# V_5.net
KiCad netlist of a schematic drawn in Altium Designer
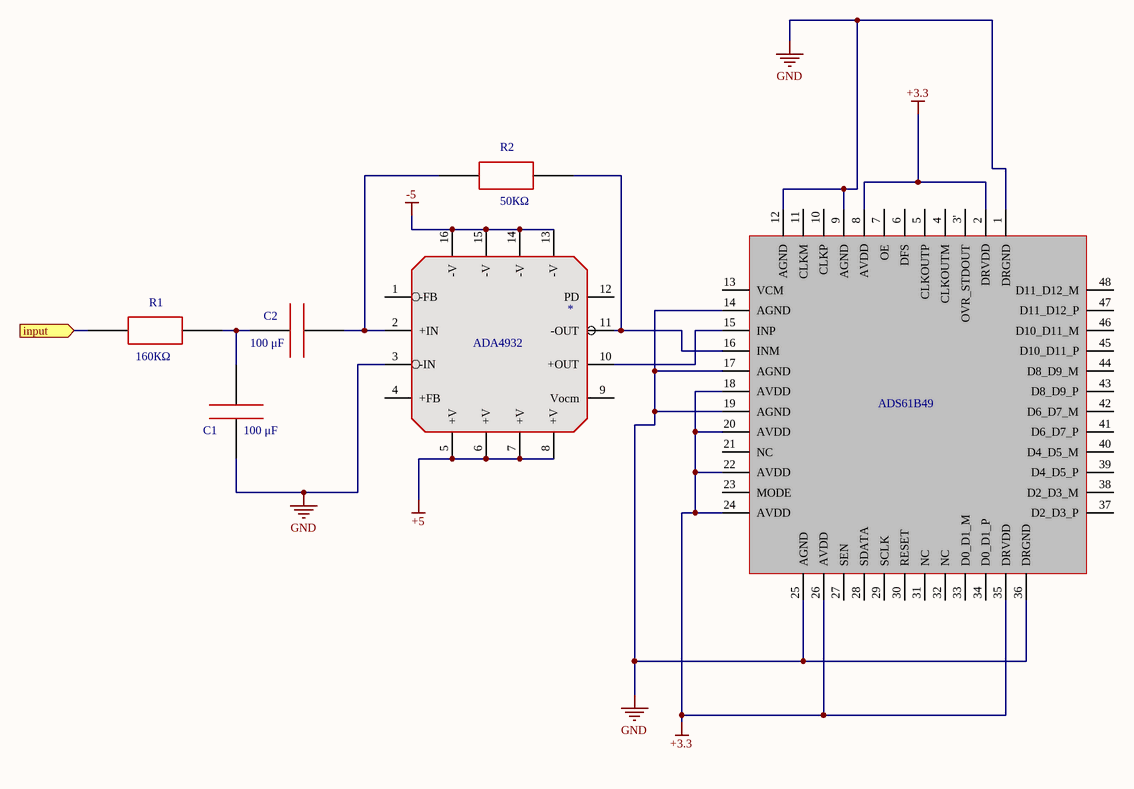
[diagram p0: V_5.SchDoc]

(export (version "E")
  (design (tool "Eeschema 10.0.6"))
  (components
    (comp (ref "ADA4932") (value "*") (footprint "ADA4932") (libsource (lib "*") (part "ADA4932")))
    (comp (ref "ADS61B49") (value "*") (footprint "ADS61B49") (libsource (lib "*") (part "ADS61B49")))
    (comp (ref "C1") (value "100 μF") (footprint "Capacitor") (libsource (lib "*") (part "Capacitor")))
    (comp (ref "C2") (value "100 μF") (footprint "Capacitor") (libsource (lib "*") (part "Capacitor")))
    (comp (ref "R1") (value "160КΩ") (footprint "Resistor") (libsource (lib "*") (part "Resistor")))
    (comp (ref "R2") (value "50КΩ") (footprint "Resistor") (libsource (lib "*") (part "Resistor")))
  )
  (nets
    (net (code "1") (name "+3.3") (class "Default")
      (node (ref "ADS61B49") (pin "18") (pinfunction "AVDD_18") (pintype "passive"))
      (node (ref "ADS61B49") (pin "2") (pinfunction "DRVDD_2") (pintype "passive"))
      (node (ref "ADS61B49") (pin "20") (pinfunction "AVDD_20") (pintype "passive"))
      (node (ref "ADS61B49") (pin "22") (pinfunction "AVDD_22") (pintype "passive"))
      (node (ref "ADS61B49") (pin "24") (pinfunction "AVDD_24") (pintype "passive"))
      (node (ref "ADS61B49") (pin "26") (pinfunction "AVDD_26") (pintype "passive"))
      (node (ref "ADS61B49") (pin "35") (pinfunction "DRVDD_35") (pintype "passive"))
      (node (ref "ADS61B49") (pin "8") (pinfunction "AVDD_8") (pintype "passive"))
    )
    (net (code "2") (name "+5") (class "Default")
      (node (ref "ADA4932") (pin "5") (pinfunction "+V_5") (pintype "passive"))
      (node (ref "ADA4932") (pin "6") (pinfunction "+V_6") (pintype "passive"))
      (node (ref "ADA4932") (pin "7") (pinfunction "+V_7") (pintype "passive"))
      (node (ref "ADA4932") (pin "8") (pinfunction "+V_8") (pintype "passive"))
    )
    (net (code "3") (name "-5") (class "Default")
      (node (ref "ADA4932") (pin "13") (pinfunction "-V_13") (pintype "passive"))
      (node (ref "ADA4932") (pin "14") (pinfunction "-V_14") (pintype "passive"))
      (node (ref "ADA4932") (pin "15") (pinfunction "-V_15") (pintype "passive"))
      (node (ref "ADA4932") (pin "16") (pinfunction "-V_16") (pintype "passive"))
    )
    (net (code "4") (name "/input") (class "Default")
      (node (ref "R1") (pin "0") (pinfunction "0_0") (pintype "passive"))
    )
    (net (code "5") (name "GND") (class "Default")
      (node (ref "ADA4932") (pin "3") (pinfunction "-IN_3") (pintype "passive"))
      (node (ref "ADS61B49") (pin "1") (pinfunction "DRGND_1") (pintype "passive"))
      (node (ref "ADS61B49") (pin "12") (pinfunction "AGND_12") (pintype "passive"))
      (node (ref "ADS61B49") (pin "14") (pinfunction "AGND_14") (pintype "passive"))
      (node (ref "ADS61B49") (pin "17") (pinfunction "AGND_17") (pintype "passive"))
      (node (ref "ADS61B49") (pin "19") (pinfunction "AGND_19") (pintype "passive"))
      (node (ref "ADS61B49") (pin "25") (pinfunction "AGND_25") (pintype "passive"))
      (node (ref "ADS61B49") (pin "36") (pinfunction "DRGND_36") (pintype "passive"))
      (node (ref "ADS61B49") (pin "9") (pinfunction "AGND_9") (pintype "passive"))
      (node (ref "C1") (pin "3") (pinfunction "3_3") (pintype "passive"))
    )
    (net (code "6") (name "Net-(ADA4932-+IN)") (class "Default")
      (node (ref "ADA4932") (pin "2") (pinfunction "+IN_2") (pintype "passive"))
      (node (ref "C2") (pin "2") (pinfunction "2_2") (pintype "passive"))
      (node (ref "R2") (pin "0") (pinfunction "0_0") (pintype "passive"))
    )
    (net (code "7") (name "Net-(ADA4932-+OUT)") (class "Default")
      (node (ref "ADA4932") (pin "10") (pinfunction "+OUT_10") (pintype "passive"))
      (node (ref "ADS61B49") (pin "15") (pinfunction "INP_15") (pintype "passive"))
    )
    (net (code "8") (name "Net-(ADA4932--OUT)") (class "Default")
      (node (ref "ADA4932") (pin "11") (pinfunction "-OUT_11") (pintype "passive"))
      (node (ref "ADS61B49") (pin "16") (pinfunction "INM_16") (pintype "passive"))
      (node (ref "R2") (pin "1") (pinfunction "1_1") (pintype "passive"))
    )
    (net (code "9") (name "Net-(C1-Pad2)") (class "Default")
      (node (ref "C1") (pin "2") (pinfunction "2_2") (pintype "passive"))
      (node (ref "C2") (pin "3") (pinfunction "3_3") (pintype "passive"))
      (node (ref "R1") (pin "1") (pinfunction "1_1") (pintype "passive"))
    )
    (net (code "10") (name "unconnected-(ADA4932-+FB-Pad4)") (class "Default")
      (node (ref "ADA4932") (pin "4") (pinfunction "+FB_4") (pintype "passive"))
    )
    (net (code "11") (name "unconnected-(ADA4932--FB-Pad1)") (class "Default")
      (node (ref "ADA4932") (pin "1") (pinfunction "-FB_1") (pintype "passive"))
    )
    (net (code "12") (name "unconnected-(ADA4932-PD-Pad12)") (class "Default")
      (node (ref "ADA4932") (pin "12") (pinfunction "PD_12") (pintype "passive"))
    )
    (net (code "13") (name "unconnected-(ADA4932-Vocm-Pad9)") (class "Default")
      (node (ref "ADA4932") (pin "9") (pinfunction "Vocm_9") (pintype "passive"))
    )
    (net (code "14") (name "unconnected-(ADS61B49-CLKM-Pad11)") (class "Default")
      (node (ref "ADS61B49") (pin "11") (pinfunction "CLKM_11") (pintype "passive"))
    )
    (net (code "15") (name "unconnected-(ADS61B49-CLKOUTM-Pad4)") (class "Default")
      (node (ref "ADS61B49") (pin "4") (pinfunction "CLKOUTM_4") (pintype "passive"))
    )
    (net (code "16") (name "unconnected-(ADS61B49-CLKOUTP-Pad5)") (class "Default")
      (node (ref "ADS61B49") (pin "5") (pinfunction "CLKOUTP_5") (pintype "passive"))
    )
    (net (code "17") (name "unconnected-(ADS61B49-CLKP-Pad10)") (class "Default")
      (node (ref "ADS61B49") (pin "10") (pinfunction "CLKP_10") (pintype "passive"))
    )
    (net (code "18") (name "unconnected-(ADS61B49-D0_D1_M-Pad33)") (class "Default")
      (node (ref "ADS61B49") (pin "33") (pinfunction "D0_D1_M_33") (pintype "passive"))
    )
    (net (code "19") (name "unconnected-(ADS61B49-D0_D1_P-Pad34)") (class "Default")
      (node (ref "ADS61B49") (pin "34") (pinfunction "D0_D1_P_34") (pintype "passive"))
    )
    (net (code "20") (name "unconnected-(ADS61B49-D2_D3_M-Pad38)") (class "Default")
      (node (ref "ADS61B49") (pin "38") (pinfunction "D2_D3_M_38") (pintype "passive"))
    )
    (net (code "21") (name "unconnected-(ADS61B49-D2_D3_P-Pad37)") (class "Default")
      (node (ref "ADS61B49") (pin "37") (pinfunction "D2_D3_P_37") (pintype "passive"))
    )
    (net (code "22") (name "unconnected-(ADS61B49-D4_D5_M-Pad40)") (class "Default")
      (node (ref "ADS61B49") (pin "40") (pinfunction "D4_D5_M_40") (pintype "passive"))
    )
    (net (code "23") (name "unconnected-(ADS61B49-D4_D5_P-Pad39)") (class "Default")
      (node (ref "ADS61B49") (pin "39") (pinfunction "D4_D5_P_39") (pintype "passive"))
    )
    (net (code "24") (name "unconnected-(ADS61B49-D6_D7_M-Pad42)") (class "Default")
      (node (ref "ADS61B49") (pin "42") (pinfunction "D6_D7_M_42") (pintype "passive"))
    )
    (net (code "25") (name "unconnected-(ADS61B49-D6_D7_P-Pad41)") (class "Default")
      (node (ref "ADS61B49") (pin "41") (pinfunction "D6_D7_P_41") (pintype "passive"))
    )
    (net (code "26") (name "unconnected-(ADS61B49-D8_D9_M-Pad44)") (class "Default")
      (node (ref "ADS61B49") (pin "44") (pinfunction "D8_D9_M_44") (pintype "passive"))
    )
    (net (code "27") (name "unconnected-(ADS61B49-D8_D9_P-Pad43)") (class "Default")
      (node (ref "ADS61B49") (pin "43") (pinfunction "D8_D9_P_43") (pintype "passive"))
    )
    (net (code "28") (name "unconnected-(ADS61B49-D10_D11_M-Pad46)") (class "Default")
      (node (ref "ADS61B49") (pin "46") (pinfunction "D10_D11_M_46") (pintype "passive"))
    )
    (net (code "29") (name "unconnected-(ADS61B49-D10_D11_P-Pad45)") (class "Default")
      (node (ref "ADS61B49") (pin "45") (pinfunction "D10_D11_P_45") (pintype "passive"))
    )
    (net (code "30") (name "unconnected-(ADS61B49-D11_D12_M-Pad48)") (class "Default")
      (node (ref "ADS61B49") (pin "48") (pinfunction "D11_D12_M_48") (pintype "passive"))
    )
    (net (code "31") (name "unconnected-(ADS61B49-D11_D12_P-Pad47)") (class "Default")
      (node (ref "ADS61B49") (pin "47") (pinfunction "D11_D12_P_47") (pintype "passive"))
    )
    (net (code "32") (name "unconnected-(ADS61B49-DFS-Pad6)") (class "Default")
      (node (ref "ADS61B49") (pin "6") (pinfunction "DFS_6") (pintype "passive"))
    )
    (net (code "33") (name "unconnected-(ADS61B49-MODE-Pad23)") (class "Default")
      (node (ref "ADS61B49") (pin "23") (pinfunction "MODE_23") (pintype "passive"))
    )
    (net (code "34") (name "unconnected-(ADS61B49-NC-Pad21)") (class "Default")
      (node (ref "ADS61B49") (pin "21") (pinfunction "NC_21") (pintype "passive"))
    )
    (net (code "35") (name "unconnected-(ADS61B49-NC-Pad31)") (class "Default")
      (node (ref "ADS61B49") (pin "31") (pinfunction "NC_31") (pintype "passive"))
    )
    (net (code "36") (name "unconnected-(ADS61B49-NC-Pad32)") (class "Default")
      (node (ref "ADS61B49") (pin "32") (pinfunction "NC_32") (pintype "passive"))
    )
    (net (code "37") (name "unconnected-(ADS61B49-OE-Pad7)") (class "Default")
      (node (ref "ADS61B49") (pin "7") (pinfunction "OE_7") (pintype "passive"))
    )
    (net (code "38") (name "unconnected-(ADS61B49-OVR_STDOUT-Pad3')") (class "Default")
      (node (ref "ADS61B49") (pin "3'") (pinfunction "OVR_STDOUT_3'") (pintype "passive"))
    )
    (net (code "39") (name "unconnected-(ADS61B49-RESET-Pad30)") (class "Default")
      (node (ref "ADS61B49") (pin "30") (pinfunction "RESET_30") (pintype "passive"))
    )
    (net (code "40") (name "unconnected-(ADS61B49-SCLK-Pad29)") (class "Default")
      (node (ref "ADS61B49") (pin "29") (pinfunction "SCLK_29") (pintype "passive"))
    )
    (net (code "41") (name "unconnected-(ADS61B49-SDATA-Pad28)") (class "Default")
      (node (ref "ADS61B49") (pin "28") (pinfunction "SDATA_28") (pintype "passive"))
    )
    (net (code "42") (name "unconnected-(ADS61B49-SEN-Pad27)") (class "Default")
      (node (ref "ADS61B49") (pin "27") (pinfunction "SEN_27") (pintype "passive"))
    )
    (net (code "43") (name "unconnected-(ADS61B49-VCM-Pad13)") (class "Default")
      (node (ref "ADS61B49") (pin "13") (pinfunction "VCM_13") (pintype "passive"))
    )
  )
)
